# MoteinoM0_mic_v0_1.net
KiCad netlist of a schematic drawn in EAGLE
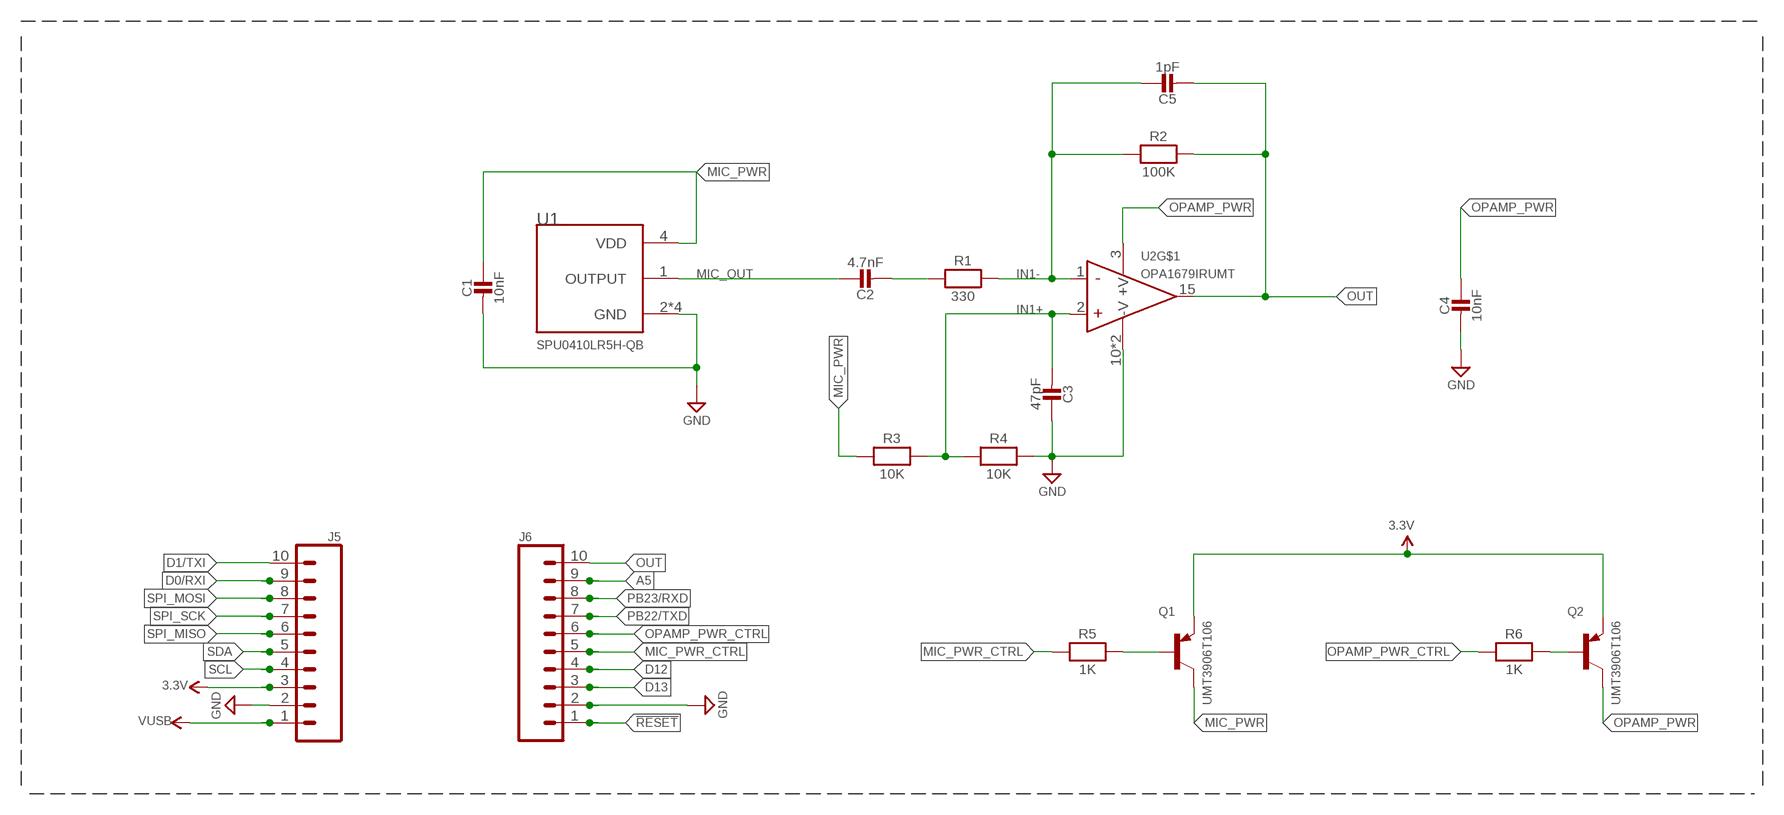
[diagram p0: schematic, sheet 1]

(export (version "E")
  (design (tool "Eeschema 10.0.6"))
  (components
    (comp (ref "C1")
      (value "10nF")
      (footprint "eagle-import:MICROBUILDER__0402MP")
      (fields (field (name "MPN") "GRM155R71H104KE14J"))
      (libsource (lib "eagle-import") (part "MICROBUILDER_CAP_CERAMIC_0402MP"))
    )
    (comp (ref "C2")
      (value "4.7nF")
      (footprint "eagle-import:MICROBUILDER__0402MP")
      (fields (field (name "MPN") "GRM155R71H104KE14J"))
      (libsource (lib "eagle-import") (part "MICROBUILDER_CAP_CERAMIC_0402MP"))
    )
    (comp (ref "C3")
      (value "47pF")
      (footprint "eagle-import:MICROBUILDER__0402MP")
      (fields (field (name "MPN") "GRM155R71H104KE14J"))
      (libsource (lib "eagle-import") (part "MICROBUILDER_CAP_CERAMIC_0402MP"))
    )
    (comp (ref "C4")
      (value "10nF")
      (footprint "eagle-import:MICROBUILDER__0402MP")
      (fields (field (name "MPN") "GRM155R71H104KE14J"))
      (libsource (lib "eagle-import") (part "MICROBUILDER_CAP_CERAMIC_0402MP"))
    )
    (comp (ref "C5")
      (value "1pF")
      (footprint "eagle-import:MICROBUILDER__0402MP")
      (fields (field (name "MPN") "GRM155R71H104KE14J"))
      (libsource (lib "eagle-import") (part "MICROBUILDER_CAP_CERAMIC_0402MP"))
    )
    (comp (ref "J5")
      (value "CONN_10NO_SILK_PTH_FEMALE")
      (footprint "eagle-import:1X10_NO_SILK")
      (libsource (lib "eagle-import") (part "CONN_10NO_SILK_PTH_FEMALE"))
    )
    (comp (ref "J6")
      (value "CONN_10NO_SILK_PTH_FEMALE")
      (footprint "eagle-import:1X10_NO_SILK")
      (libsource (lib "eagle-import") (part "CONN_10NO_SILK_PTH_FEMALE"))
    )
    (comp (ref "Q1")
      (value "UMT3906T106")
      (footprint "eagle-import:SOT65P210X100-3N-PNP")
      (libsource (lib "eagle-import") (part "UMT3906T106"))
    )
    (comp (ref "Q2")
      (value "UMT3906T106")
      (footprint "eagle-import:SOT65P210X100-3N-PNP")
      (libsource (lib "eagle-import") (part "UMT3906T106"))
    )
    (comp (ref "R1")
      (value "330")
      (footprint "eagle-import:MICROBUILDER__0402MP")
      (fields (field (name "MPN") "RC0402FR-074K7P"))
      (libsource (lib "eagle-import") (part "MICROBUILDER_RESISTOR_0402MP"))
    )
    (comp (ref "R2")
      (value "100K")
      (footprint "eagle-import:MICROBUILDER__0402MP")
      (fields (field (name "MPN") "RC0402FR-074K7P"))
      (libsource (lib "eagle-import") (part "MICROBUILDER_RESISTOR_0402MP"))
    )
    (comp (ref "R3")
      (value "10K")
      (footprint "eagle-import:MICROBUILDER__0402MP")
      (fields (field (name "MPN") "RC0402FR-074K7P"))
      (libsource (lib "eagle-import") (part "MICROBUILDER_RESISTOR_0402MP"))
    )
    (comp (ref "R4")
      (value "10K")
      (footprint "eagle-import:MICROBUILDER__0402MP")
      (fields (field (name "MPN") "RC0402FR-074K7P"))
      (libsource (lib "eagle-import") (part "MICROBUILDER_RESISTOR_0402MP"))
    )
    (comp (ref "R5")
      (value "1K")
      (footprint "eagle-import:MICROBUILDER__0402MP")
      (fields (field (name "MPN") "RC0402FR-074K7P"))
      (libsource (lib "eagle-import") (part "MICROBUILDER_RESISTOR_0402MP"))
    )
    (comp (ref "R6")
      (value "1K")
      (footprint "eagle-import:MICROBUILDER__0402MP")
      (fields (field (name "MPN") "RC0402FR-074K7P"))
      (libsource (lib "eagle-import") (part "MICROBUILDER_RESISTOR_0402MP"))
    )
    (comp (ref "U1")
      (value "SPU0410LR5H-QB")
      (footprint "eagle-import:XDCR_SPU0410LR5H-QB")
      (fields (field (name "MF") "Knowles"))
      (libsource (lib "eagle-import") (part "SPU0410LR5H-QB"))
    )
    (comp (ref "U2")
      (value "OPA1679IRUMT")
      (footprint "eagle-import:QFN65P400X400X80-17N")
      (libsource (lib "eagle-import") (part "OPA1679IRUMT"))
    )
  )
  (nets
    (net (code "1") (name "/IN1+") (class "Default")
      (node (ref "C3") (pin "2") (pinfunction "2_2") (pintype "passive"))
      (node (ref "R3") (pin "2") (pinfunction "2_2") (pintype "passive"))
      (node (ref "R4") (pin "1") (pinfunction "1_1") (pintype "passive"))
      (node (ref "U2") (pin "2") (pinfunction "+IN_2") (pintype "input"))
    )
    (net (code "2") (name "/IN1-") (class "Default")
      (node (ref "C5") (pin "1") (pinfunction "1_1") (pintype "passive"))
      (node (ref "R1") (pin "2") (pinfunction "2_2") (pintype "passive"))
      (node (ref "R2") (pin "1") (pinfunction "1_1") (pintype "passive"))
      (node (ref "U2") (pin "1") (pinfunction "-IN_1") (pintype "input"))
    )
    (net (code "3") (name "/MIC_OUT") (class "Default")
      (node (ref "C2") (pin "1") (pinfunction "1_1") (pintype "passive"))
      (node (ref "U1") (pin "1") (pinfunction "OUTPUT_1") (pintype "output"))
    )
    (net (code "4") (name "/~{RESET}") (class "Default")
      (node (ref "J6") (pin "1") (pinfunction "1_1") (pintype "passive"))
    )
    (net (code "5") (name "3.3V") (class "Default")
      (node (ref "J5") (pin "3") (pinfunction "3_3") (pintype "passive"))
      (node (ref "Q1") (pin "1") (pinfunction "E_1") (pintype "passive"))
      (node (ref "Q2") (pin "1") (pinfunction "E_1") (pintype "passive"))
    )
    (net (code "6") (name "A5") (class "Default")
      (node (ref "J6") (pin "9") (pinfunction "9_9") (pintype "passive"))
    )
    (net (code "7") (name "D0{slash}RXI") (class "Default")
      (node (ref "J5") (pin "9") (pinfunction "9_9") (pintype "passive"))
    )
    (net (code "8") (name "D1{slash}TXI") (class "Default")
      (node (ref "J5") (pin "10") (pinfunction "10_10") (pintype "passive"))
    )
    (net (code "9") (name "D12") (class "Default")
      (node (ref "J6") (pin "4") (pinfunction "4_4") (pintype "passive"))
    )
    (net (code "10") (name "D13") (class "Default")
      (node (ref "J6") (pin "3") (pinfunction "3_3") (pintype "passive"))
    )
    (net (code "11") (name "GND") (class "Default")
      (node (ref "C1") (pin "2") (pinfunction "2_2") (pintype "passive"))
      (node (ref "C3") (pin "1") (pinfunction "1_1") (pintype "passive"))
      (node (ref "C4") (pin "2") (pinfunction "2_2") (pintype "passive"))
      (node (ref "J5") (pin "2") (pinfunction "2_2") (pintype "passive"))
      (node (ref "J6") (pin "2") (pinfunction "2_2") (pintype "passive"))
      (node (ref "R4") (pin "2") (pinfunction "2_2") (pintype "passive"))
      (node (ref "U1") (pin "2") (pinfunction "GND_2") (pintype "power_in"))
      (node (ref "U1") (pin "3") (pinfunction "GND_3") (pintype "power_in"))
      (node (ref "U1") (pin "5") (pinfunction "GND_5") (pintype "power_in"))
      (node (ref "U1") (pin "6") (pinfunction "GND_6") (pintype "power_in"))
      (node (ref "U2") (pin "10") (pinfunction "-V_10") (pintype "power_in"))
      (node (ref "U2") (pin "17") (pinfunction "-V_17") (pintype "power_in"))
    )
    (net (code "12") (name "MIC_PWR") (class "Default")
      (node (ref "C1") (pin "1") (pinfunction "1_1") (pintype "passive"))
      (node (ref "Q1") (pin "3") (pinfunction "C_3") (pintype "passive"))
      (node (ref "R3") (pin "1") (pinfunction "1_1") (pintype "passive"))
      (node (ref "U1") (pin "4") (pinfunction "VDD_4") (pintype "power_in"))
    )
    (net (code "13") (name "MIC_PWR_CTRL") (class "Default")
      (node (ref "J6") (pin "5") (pinfunction "5_5") (pintype "passive"))
      (node (ref "R5") (pin "1") (pinfunction "1_1") (pintype "passive"))
    )
    (net (code "14") (name "Net-(C2-Pad2)") (class "Default")
      (node (ref "C2") (pin "2") (pinfunction "2_2") (pintype "passive"))
      (node (ref "R1") (pin "1") (pinfunction "1_1") (pintype "passive"))
    )
    (net (code "15") (name "Net-(Q1-B)") (class "Default")
      (node (ref "Q1") (pin "2") (pinfunction "B_2") (pintype "passive"))
      (node (ref "R5") (pin "2") (pinfunction "2_2") (pintype "passive"))
    )
    (net (code "16") (name "Net-(Q2-B)") (class "Default")
      (node (ref "Q2") (pin "2") (pinfunction "B_2") (pintype "passive"))
      (node (ref "R6") (pin "2") (pinfunction "2_2") (pintype "passive"))
    )
    (net (code "17") (name "OPAMP_PWR") (class "Default")
      (node (ref "C4") (pin "1") (pinfunction "1_1") (pintype "passive"))
      (node (ref "Q2") (pin "3") (pinfunction "C_3") (pintype "passive"))
      (node (ref "U2") (pin "3") (pinfunction "+V_3") (pintype "power_in"))
    )
    (net (code "18") (name "OPAMP_PWR_CTRL") (class "Default")
      (node (ref "J6") (pin "6") (pinfunction "6_6") (pintype "passive"))
      (node (ref "R6") (pin "1") (pinfunction "1_1") (pintype "passive"))
    )
    (net (code "19") (name "OUT") (class "Default")
      (node (ref "C5") (pin "2") (pinfunction "2_2") (pintype "passive"))
      (node (ref "J6") (pin "10") (pinfunction "10_10") (pintype "passive"))
      (node (ref "R2") (pin "2") (pinfunction "2_2") (pintype "passive"))
      (node (ref "U2") (pin "15") (pinfunction "OUT_15") (pintype "output"))
    )
    (net (code "20") (name "PB22{slash}TXD") (class "Default")
      (node (ref "J6") (pin "7") (pinfunction "7_7") (pintype "passive"))
    )
    (net (code "21") (name "PB23{slash}RXD") (class "Default")
      (node (ref "J6") (pin "8") (pinfunction "8_8") (pintype "passive"))
    )
    (net (code "22") (name "SCL") (class "Default")
      (node (ref "J5") (pin "4") (pinfunction "4_4") (pintype "passive"))
    )
    (net (code "23") (name "SDA") (class "Default")
      (node (ref "J5") (pin "5") (pinfunction "5_5") (pintype "passive"))
    )
    (net (code "24") (name "SPI_MISO") (class "Default")
      (node (ref "J5") (pin "6") (pinfunction "6_6") (pintype "passive"))
    )
    (net (code "25") (name "SPI_MOSI") (class "Default")
      (node (ref "J5") (pin "8") (pinfunction "8_8") (pintype "passive"))
    )
    (net (code "26") (name "SPI_SCK") (class "Default")
      (node (ref "J5") (pin "7") (pinfunction "7_7") (pintype "passive"))
    )
    (net (code "27") (name "VUSB") (class "Default")
      (node (ref "J5") (pin "1") (pinfunction "1_1") (pintype "passive"))
    )
  )
)
